# Programmer_v1_0.net
KiCad netlist of a schematic drawn in EAGLE
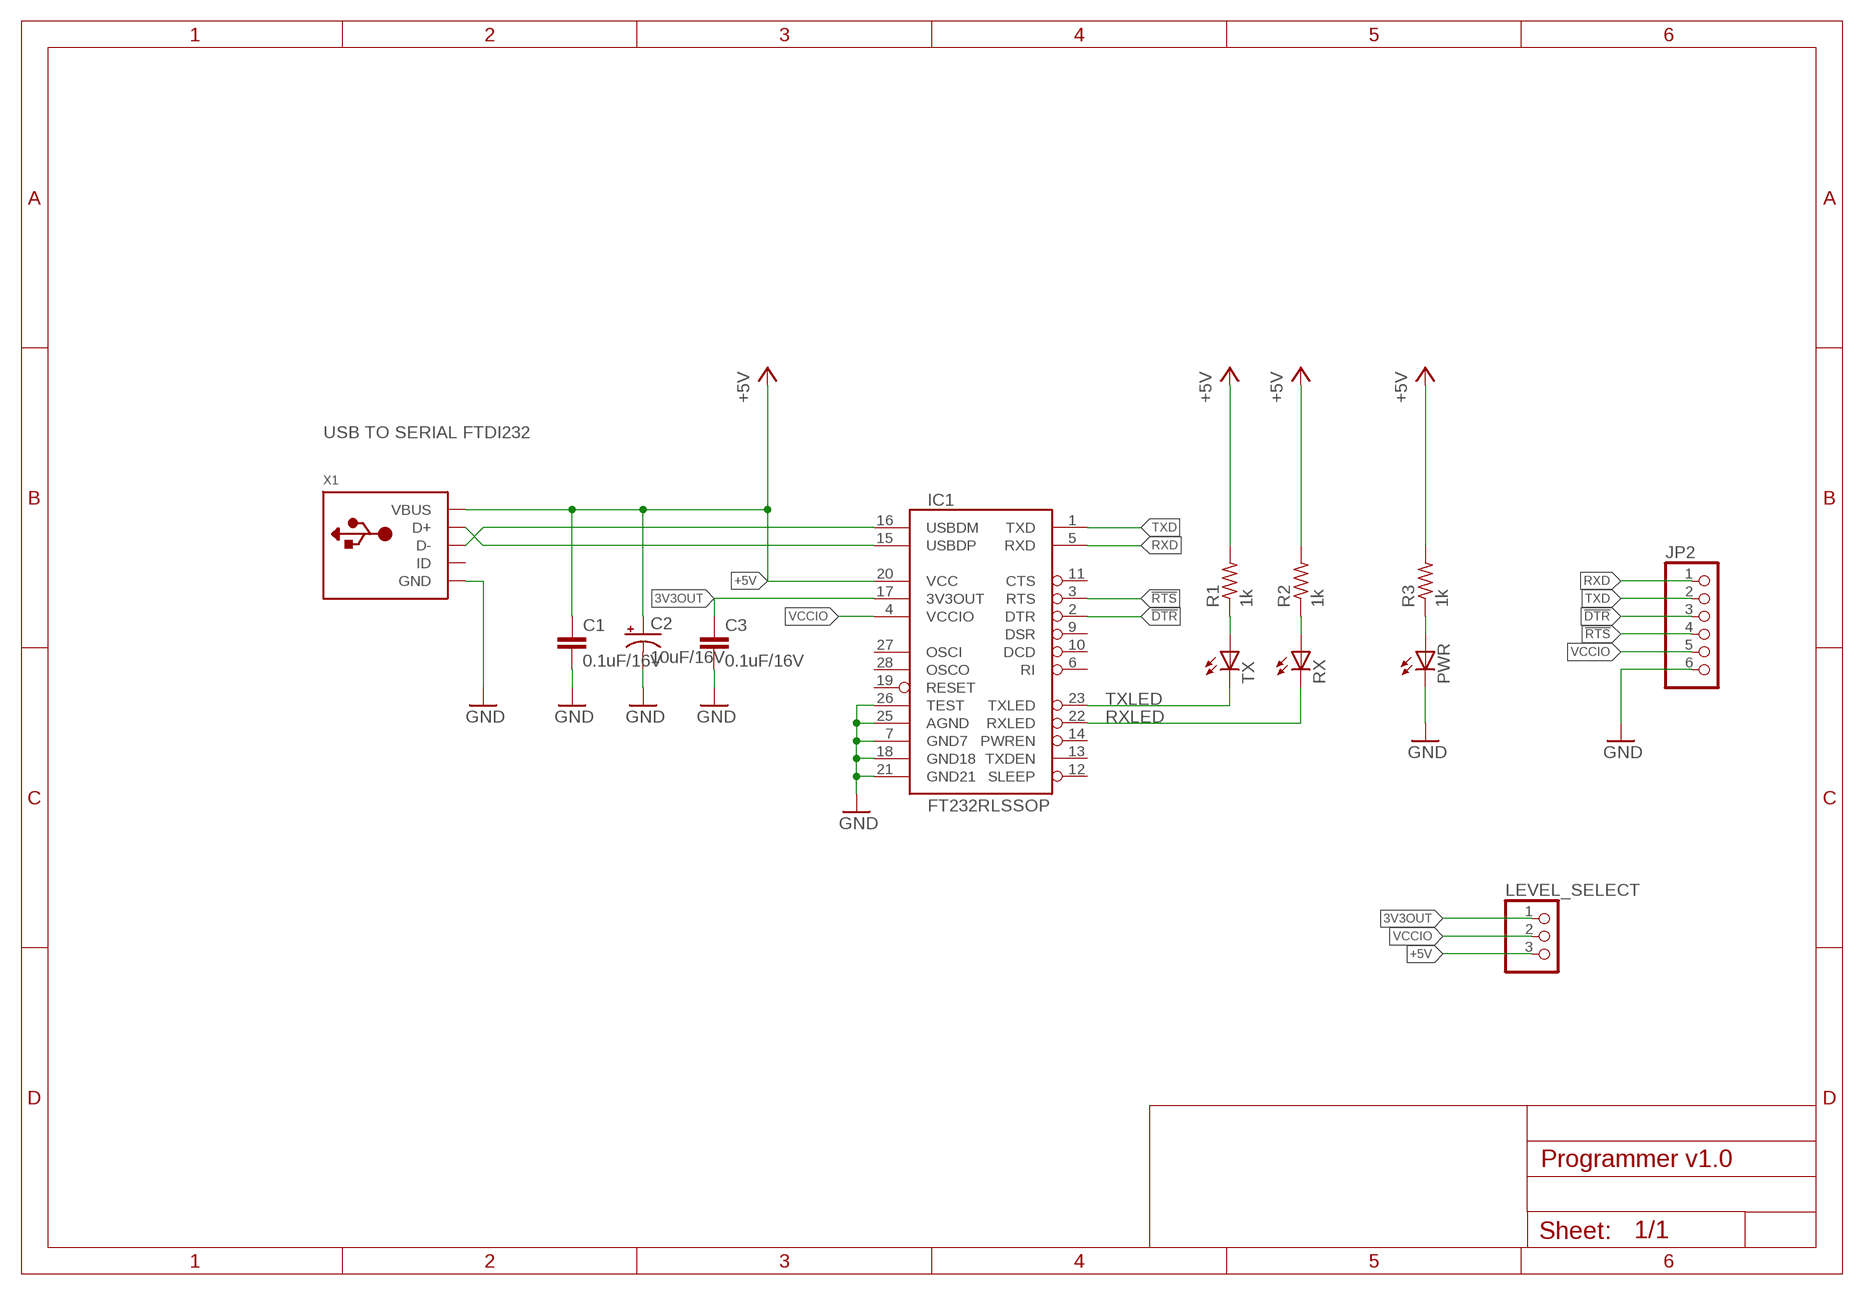
[diagram p0: schematic, sheet 1]

(export (version "E")
  (design (tool "Eeschema 10.0.6"))
  (components
    (comp (ref "C1")
      (value "0.1uF/16V")
      (footprint "eagle-import:C0805K")
      (libsource (lib "eagle-import") (part "C-EUC0805K"))
    )
    (comp (ref "C2")
      (value "10uF/16V")
      (footprint "eagle-import:SPARKFUN_EIA3216")
      (libsource (lib "eagle-import") (part "SPARKFUN_CAP_POL1206"))
    )
    (comp (ref "C3")
      (value "0.1uF/16V")
      (footprint "eagle-import:C0805K")
      (libsource (lib "eagle-import") (part "C-EUC0805K"))
    )
    (comp (ref "IC1")
      (value "FT232RLSSOP")
      (footprint "eagle-import:SSOP28DB")
      (libsource (lib "eagle-import") (part "FT232RLSSOP"))
    )
    (comp (ref "JP2")
      (value "PINHD-1X6")
      (footprint "eagle-import:1X06")
      (libsource (lib "eagle-import") (part "PINHD-1X6"))
    )
    (comp (ref "LEVEL_SELECT")
      (value "PINHD-1X3")
      (footprint "eagle-import:1X03")
      (libsource (lib "eagle-import") (part "PINHD-1X3"))
    )
    (comp (ref "PWR")
      (value "LEDCHIP-LED0805")
      (footprint "eagle-import:CHIP-LED0805")
      (libsource (lib "eagle-import") (part "LEDCHIP-LED0805"))
    )
    (comp (ref "R1")
      (value "1k")
      (footprint "eagle-import:M0805")
      (libsource (lib "eagle-import") (part "R-US_M0805"))
    )
    (comp (ref "R2")
      (value "1k")
      (footprint "eagle-import:M0805")
      (libsource (lib "eagle-import") (part "R-US_M0805"))
    )
    (comp (ref "R3")
      (value "1k")
      (footprint "eagle-import:M0805")
      (libsource (lib "eagle-import") (part "R-US_M0805"))
    )
    (comp (ref "RX")
      (value "LEDCHIP-LED0805")
      (footprint "eagle-import:CHIP-LED0805")
      (libsource (lib "eagle-import") (part "LEDCHIP-LED0805"))
    )
    (comp (ref "TX")
      (value "LEDCHIP-LED0805")
      (footprint "eagle-import:CHIP-LED0805")
      (libsource (lib "eagle-import") (part "LEDCHIP-LED0805"))
    )
    (comp (ref "X1")
      (value "USB_MICRO_20329_V2")
      (footprint "eagle-import:4UCONN_20329_V2")
      (libsource (lib "eagle-import") (part "USB_MICRO_20329_V2"))
    )
  )
  (nets
    (net (code "1") (name "+5V") (class "Default")
      (node (ref "C1") (pin "1") (pinfunction "1_1") (pintype "passive"))
      (node (ref "C2") (pin "A") (pinfunction "+_A") (pintype "passive"))
      (node (ref "IC1") (pin "20") (pinfunction "VCC_20") (pintype "power_in"))
      (node (ref "LEVEL_SELECT") (pin "3") (pinfunction "3_3") (pintype "passive"))
      (node (ref "R1") (pin "2") (pinfunction "2_2") (pintype "passive"))
      (node (ref "R2") (pin "2") (pinfunction "2_2") (pintype "passive"))
      (node (ref "R3") (pin "2") (pinfunction "2_2") (pintype "passive"))
      (node (ref "X1") (pin "VBUS") (pinfunction "VBUS_VBUS") (pintype "power_in"))
    )
    (net (code "2") (name "/RXLED") (class "Default")
      (node (ref "IC1") (pin "22") (pinfunction "RXLED_22") (pintype "input"))
      (node (ref "RX") (pin "C") (pinfunction "C_C") (pintype "passive"))
    )
    (net (code "3") (name "/TXLED") (class "Default")
      (node (ref "IC1") (pin "23") (pinfunction "TXLED_23") (pintype "input"))
      (node (ref "TX") (pin "C") (pinfunction "C_C") (pintype "passive"))
    )
    (net (code "4") (name "/~{DTR}") (class "Default")
      (node (ref "IC1") (pin "2") (pinfunction "DTR_2") (pintype "output"))
      (node (ref "JP2") (pin "3") (pinfunction "3_3") (pintype "passive"))
    )
    (net (code "5") (name "/~{RTS}") (class "Default")
      (node (ref "IC1") (pin "3") (pinfunction "RTS_3") (pintype "output"))
      (node (ref "JP2") (pin "4") (pinfunction "4_4") (pintype "passive"))
    )
    (net (code "6") (name "3V3OUT") (class "Default")
      (node (ref "C3") (pin "1") (pinfunction "1_1") (pintype "passive"))
      (node (ref "IC1") (pin "17") (pinfunction "3V3OUT_17") (pintype "output"))
      (node (ref "LEVEL_SELECT") (pin "1") (pinfunction "1_1") (pintype "passive"))
    )
    (net (code "7") (name "GND") (class "Default")
      (node (ref "C1") (pin "2") (pinfunction "2_2") (pintype "passive"))
      (node (ref "C2") (pin "C") (pinfunction "-_C") (pintype "passive"))
      (node (ref "C3") (pin "2") (pinfunction "2_2") (pintype "passive"))
      (node (ref "IC1") (pin "18") (pinfunction "GND18_18") (pintype "power_in"))
      (node (ref "IC1") (pin "21") (pinfunction "GND21_21") (pintype "power_in"))
      (node (ref "IC1") (pin "25") (pinfunction "AGND_25") (pintype "power_in"))
      (node (ref "IC1") (pin "26") (pinfunction "TEST_26") (pintype "input"))
      (node (ref "IC1") (pin "7") (pinfunction "GND7_7") (pintype "power_in"))
      (node (ref "JP2") (pin "6") (pinfunction "6_6") (pintype "passive"))
      (node (ref "PWR") (pin "C") (pinfunction "C_C") (pintype "passive"))
      (node (ref "X1") (pin "BASE@1") (pinfunction "GND_BASE@1") (pintype "power_in"))
      (node (ref "X1") (pin "BASE@2") (pinfunction "GND_BASE@2") (pintype "power_in"))
      (node (ref "X1") (pin "GND") (pinfunction "GND_GND") (pintype "power_in"))
      (node (ref "X1") (pin "SPRT@1") (pinfunction "GND_SPRT@1") (pintype "power_in"))
      (node (ref "X1") (pin "SPRT@2") (pinfunction "GND_SPRT@2") (pintype "power_in"))
      (node (ref "X1") (pin "SPRT@3") (pinfunction "GND_SPRT@3") (pintype "power_in"))
      (node (ref "X1") (pin "SPRT@4") (pinfunction "GND_SPRT@4") (pintype "power_in"))
    )
    (net (code "8") (name "Net-(IC1-USBDM)") (class "Default")
      (node (ref "IC1") (pin "16") (pinfunction "USBDM_16") (pintype "bidirectional"))
      (node (ref "X1") (pin "D-") (pinfunction "D-_D-") (pintype "bidirectional"))
    )
    (net (code "9") (name "Net-(IC1-USBDP)") (class "Default")
      (node (ref "IC1") (pin "15") (pinfunction "USBDP_15") (pintype "bidirectional"))
      (node (ref "X1") (pin "D+") (pinfunction "D+_D+") (pintype "bidirectional"))
    )
    (net (code "10") (name "Net-(PWR-PadA)") (class "Default")
      (node (ref "PWR") (pin "A") (pinfunction "A_A") (pintype "passive"))
      (node (ref "R3") (pin "1") (pinfunction "1_1") (pintype "passive"))
    )
    (net (code "11") (name "Net-(R1-Pad1)") (class "Default")
      (node (ref "R1") (pin "1") (pinfunction "1_1") (pintype "passive"))
      (node (ref "TX") (pin "A") (pinfunction "A_A") (pintype "passive"))
    )
    (net (code "12") (name "Net-(R2-Pad1)") (class "Default")
      (node (ref "R2") (pin "1") (pinfunction "1_1") (pintype "passive"))
      (node (ref "RX") (pin "A") (pinfunction "A_A") (pintype "passive"))
    )
    (net (code "13") (name "RXD") (class "Default")
      (node (ref "IC1") (pin "5") (pinfunction "RXD_5") (pintype "input"))
      (node (ref "JP2") (pin "1") (pinfunction "1_1") (pintype "passive"))
    )
    (net (code "14") (name "TXD") (class "Default")
      (node (ref "IC1") (pin "1") (pinfunction "TXD_1") (pintype "output"))
      (node (ref "JP2") (pin "2") (pinfunction "2_2") (pintype "passive"))
    )
    (net (code "15") (name "VCCIO") (class "Default")
      (node (ref "IC1") (pin "4") (pinfunction "VCCIO_4") (pintype "power_in"))
      (node (ref "JP2") (pin "5") (pinfunction "5_5") (pintype "passive"))
      (node (ref "LEVEL_SELECT") (pin "2") (pinfunction "2_2") (pintype "passive"))
    )
    (net (code "16") (name "unconnected-(IC1-CTS-Pad11)") (class "Default")
      (node (ref "IC1") (pin "11") (pinfunction "CTS_11") (pintype "input"))
    )
    (net (code "17") (name "unconnected-(IC1-DCD-Pad10)") (class "Default")
      (node (ref "IC1") (pin "10") (pinfunction "DCD_10") (pintype "input"))
    )
    (net (code "18") (name "unconnected-(IC1-DSR-Pad9)") (class "Default")
      (node (ref "IC1") (pin "9") (pinfunction "DSR_9") (pintype "input"))
    )
    (net (code "19") (name "unconnected-(IC1-OSCI-Pad27)") (class "Default")
      (node (ref "IC1") (pin "27") (pinfunction "OSCI_27") (pintype "input"))
    )
    (net (code "20") (name "unconnected-(IC1-OSCO-Pad28)") (class "Default")
      (node (ref "IC1") (pin "28") (pinfunction "OSCO_28") (pintype "output"))
    )
    (net (code "21") (name "unconnected-(IC1-PWREN-Pad14)") (class "Default")
      (node (ref "IC1") (pin "14") (pinfunction "PWREN_14") (pintype "input"))
    )
    (net (code "22") (name "unconnected-(IC1-RESET-Pad19)") (class "Default")
      (node (ref "IC1") (pin "19") (pinfunction "RESET_19") (pintype "input"))
    )
    (net (code "23") (name "unconnected-(IC1-RI-Pad6)") (class "Default")
      (node (ref "IC1") (pin "6") (pinfunction "RI_6") (pintype "input"))
    )
    (net (code "24") (name "unconnected-(IC1-SLEEP-Pad12)") (class "Default")
      (node (ref "IC1") (pin "12") (pinfunction "SLEEP_12") (pintype "input"))
    )
    (net (code "25") (name "unconnected-(IC1-TXDEN-Pad13)") (class "Default")
      (node (ref "IC1") (pin "13") (pinfunction "TXDEN_13") (pintype "input"))
    )
    (net (code "26") (name "unconnected-(X1-PadID)") (class "Default")
      (node (ref "X1") (pin "ID") (pinfunction "ID_ID") (pintype "bidirectional"))
    )
  )
)
